# Nuio_Left_Keyboard_Rev_H_KeyboardNRF.net
KiCad netlist of a schematic drawn in Altium Designer
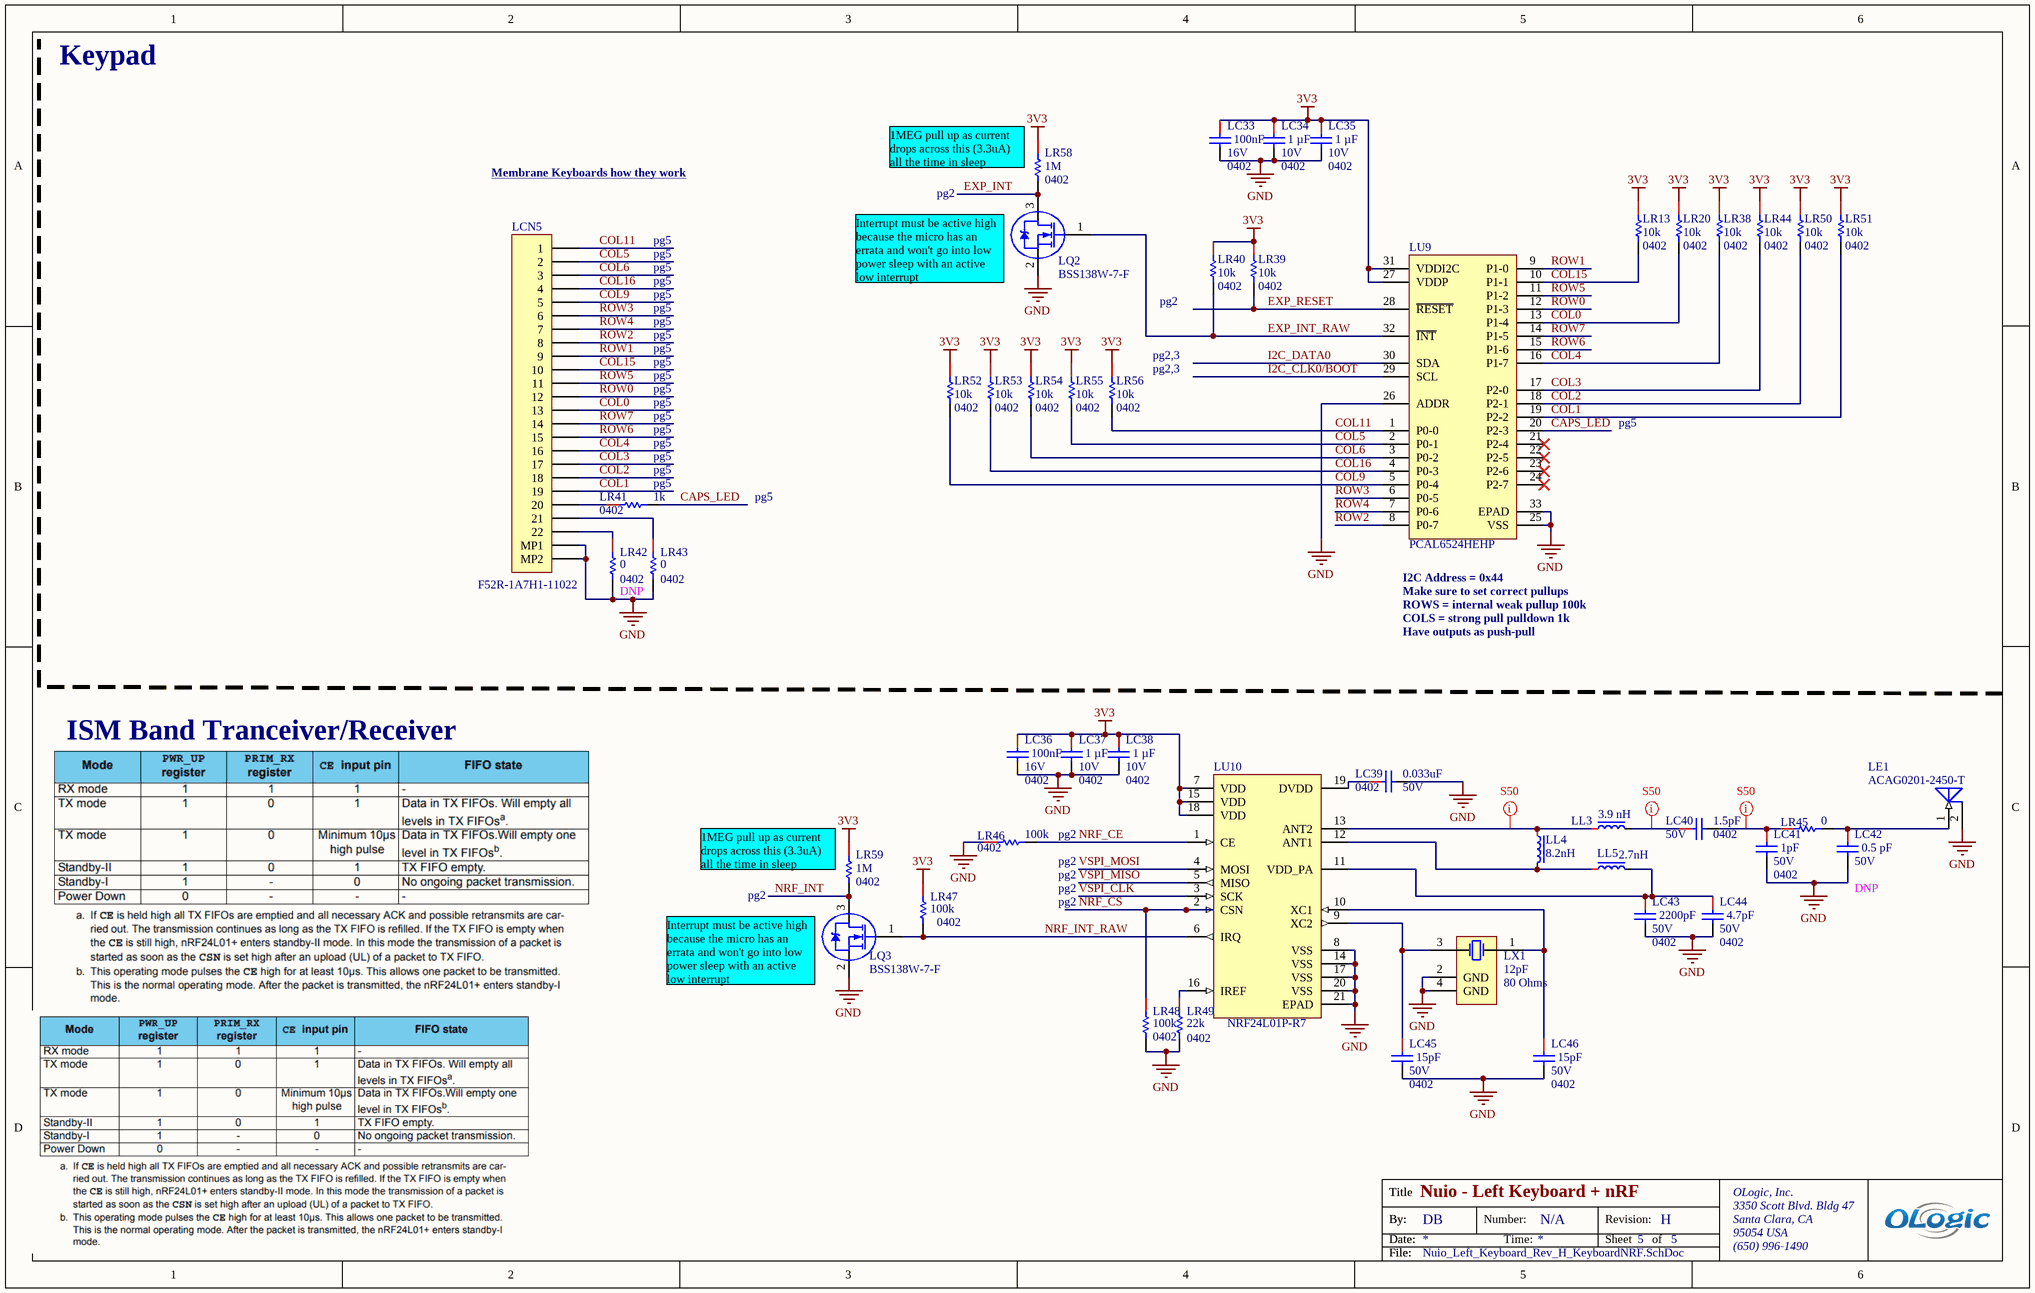
[diagram p0: Nuio_Left_Keyboard_Rev_H_KeyboardNRF.SchDoc]

(export (version "E")
  (design (tool "Eeschema 10.0.6"))
  (components
    (comp (ref "LC33")
      (value "CAP CER 0.1UF 16V X5R 0402")
      (footprint "CAPC0402(1005)_L")
      (description "±10% 16V Ceramic Capacitor X5R 0402 (1005 Metric)")
      (fields
        (field (name "PACKAGE (IMPERIAL)") "0402")
        (field (name "VOLTAGE (RATED)") "16V")
        (field (name "CAPACITANCE") "100nF")
        (field (name "MANUFACTURER") "Taiyo Yuden")
        (field (name "MANUFACTURER PART NUMBER") "EMK105BJ104KV-F")
      )
      (libsource (lib "OLogic Nexus Vault") (part "OL_Capacitor"))
    )
    (comp (ref "LC34")
      (value "CAP CER 1UF 10V X5R 0402")
      (footprint "CAPC0402(1005)_L")
      (description "±20% 10V Ceramic Capacitor X5R 0402 (1005 Metric)")
      (fields
        (field (name "PACKAGE (IMPERIAL)") "0402")
        (field (name "VOLTAGE (RATED)") "10V")
        (field (name "CAPACITANCE") "1 µF")
        (field (name "MANUFACTURER PART NUMBER") "CC0402MRX5R6BB105")
        (field (name "TOLERANCE") "±20%")
      )
      (libsource (lib "OLogic Nexus Vault") (part "OL_Capacitor"))
    )
    (comp (ref "LC35")
      (value "CAP CER 1UF 10V X5R 0402")
      (footprint "CAPC0402(1005)_L")
      (description "±20% 10V Ceramic Capacitor X5R 0402 (1005 Metric)")
      (fields
        (field (name "PACKAGE (IMPERIAL)") "0402")
        (field (name "VOLTAGE (RATED)") "10V")
        (field (name "CAPACITANCE") "1 µF")
        (field (name "MANUFACTURER PART NUMBER") "CC0402MRX5R6BB105")
        (field (name "TOLERANCE") "±20%")
      )
      (libsource (lib "OLogic Nexus Vault") (part "OL_Capacitor"))
    )
    (comp (ref "LC36")
      (value "CAP CER 0.1UF 16V X5R 0402")
      (footprint "CAPC0402(1005)_L")
      (description "±10% 16V Ceramic Capacitor X5R 0402 (1005 Metric)")
      (fields
        (field (name "PACKAGE (IMPERIAL)") "0402")
        (field (name "VOLTAGE (RATED)") "16V")
        (field (name "CAPACITANCE") "100nF")
        (field (name "MANUFACTURER") "Taiyo Yuden")
        (field (name "MANUFACTURER PART NUMBER") "EMK105BJ104KV-F")
      )
      (libsource (lib "OLogic Nexus Vault") (part "OL_Capacitor"))
    )
    (comp (ref "LC37")
      (value "CAP CER 1UF 10V X5R 0402")
      (footprint "CAPC0402(1005)_L")
      (description "±20% 10V Ceramic Capacitor X5R 0402 (1005 Metric)")
      (fields
        (field (name "PACKAGE (IMPERIAL)") "0402")
        (field (name "VOLTAGE (RATED)") "10V")
        (field (name "CAPACITANCE") "1 µF")
        (field (name "MANUFACTURER PART NUMBER") "CC0402MRX5R6BB105")
        (field (name "TOLERANCE") "±20%")
      )
      (libsource (lib "OLogic Nexus Vault") (part "OL_Capacitor"))
    )
    (comp (ref "LC38")
      (value "CAP CER 1UF 10V X5R 0402")
      (footprint "CAPC0402(1005)_L")
      (description "±20% 10V Ceramic Capacitor X5R 0402 (1005 Metric)")
      (fields
        (field (name "PACKAGE (IMPERIAL)") "0402")
        (field (name "VOLTAGE (RATED)") "10V")
        (field (name "CAPACITANCE") "1 µF")
        (field (name "MANUFACTURER PART NUMBER") "CC0402MRX5R6BB105")
        (field (name "TOLERANCE") "±20%")
      )
      (libsource (lib "OLogic Nexus Vault") (part "OL_Capacitor"))
    )
    (comp (ref "LC39")
      (value "0.033uF")
      (footprint "CAPC0402(1005)_L")
      (description "CAP CER 0.033UF 50V 10% X7R 0402")
      (fields
        (field (name "VOLTAGE (RATED)") "50V")
        (field (name "PACKAGE (IMPERIAL)") "0402")
        (field (name "TOLERANCE") "10%")
      )
      (libsource (lib "OLogic Nexus Vault") (part "=Capacitance"))
    )
    (comp (ref "LC40")
      (value "1.5pF")
      (footprint "CAPC0402(1005)_L")
      (description "CAP CER 1.5PF 50V NP0 0402")
      (fields
        (field (name "VOLTAGE (RATED)") "50V")
        (field (name "PACKAGE (IMPERIAL)") "0402")
        (field (name "TOLERANCE") "5%")
      )
      (libsource (lib "OLogic Nexus Vault") (part "=Capacitance"))
    )
    (comp (ref "LC41")
      (value "1pF")
      (footprint "CAPC0402(1005)_L")
      (description "CAP CER 1PF 50V NP0 0402")
      (fields
        (field (name "VOLTAGE (RATED)") "50V")
        (field (name "PACKAGE (IMPERIAL)") "0402")
        (field (name "TOLERANCE") "5%")
      )
      (libsource (lib "OLogic Nexus Vault") (part "=Capacitance"))
    )
    (comp (ref "LC42")
      (value "CAP CER 0.5PF 50V C0G/NP0 0402")
      (footprint "CAPC0402(1005)_L")
      (description "0.5 pF ±0.1pF 50V Ceramic Capacitor C0G, NP0 0402 (1005 Metric)")
      (fields
        (field (name "CAPACITANCE") "0.5 pF")
        (field (name "VOLTAGE - RATED") "50V")
        (field (name "TOLERANCE") "±0.1pF")
        (field (name "MANUFACTURER PART NUMBER") "QSCF500Q0R5B1GV001T")
      )
      (libsource (lib "OLogic Nexus Vault") (part "OL_Capacitor"))
    )
    (comp (ref "LC43")
      (value "2200pF")
      (footprint "CAPC0402(1005)_L")
      (description "CAP CER 2200PF 50V 10% X7R 0402")
      (fields
        (field (name "VOLTAGE (RATED)") "50V")
        (field (name "PACKAGE (IMPERIAL)") "0402")
        (field (name "TOLERANCE") "10%")
      )
      (libsource (lib "OLogic Nexus Vault") (part "=Capacitance"))
    )
    (comp (ref "LC44")
      (value "4.7pF")
      (footprint "CAPC0402(1005)_L")
      (description "CAP CER 4.7pF 50V 5% NP0 0402")
      (fields
        (field (name "VOLTAGE (RATED)") "50V")
        (field (name "PACKAGE (IMPERIAL)") "0402")
        (field (name "TOLERANCE") "5%")
      )
      (libsource (lib "OLogic Nexus Vault") (part "=Capacitance"))
    )
    (comp (ref "LC45")
      (value "15pF")
      (footprint "CAPC0402(1005)_L")
      (description "CAP CER 15PF 50V C0G/NP0 0402")
      (fields
        (field (name "VOLTAGE (RATED)") "50V")
        (field (name "PACKAGE (IMPERIAL)") "0402")
        (field (name "TOLERANCE") "5%")
      )
      (libsource (lib "OLogic Nexus Vault") (part "=Capacitance"))
    )
    (comp (ref "LC46")
      (value "15pF")
      (footprint "CAPC0402(1005)_L")
      (description "CAP CER 15PF 50V C0G/NP0 0402")
      (fields
        (field (name "VOLTAGE (RATED)") "50V")
        (field (name "PACKAGE (IMPERIAL)") "0402")
        (field (name "TOLERANCE") "5%")
      )
      (libsource (lib "OLogic Nexus Vault") (part "=Capacitance"))
    )
    (comp (ref "LCN5")
      (value "F52R-1A7H1-11022")
      (footprint "F52R-1A7H1-11022")
      (description "FLEX CONNECTOR, 1.00MM PITCH, HE")
      (fields (field (name "MANUFACTURER") "Amphenol ICC (FCI)"))
      (libsource (lib "OLogic Nexus Vault") (part "F52R-1A7H1-11022"))
    )
    (comp (ref "LE1")
      (value "ACAG0201-2450-T")
      (footprint "ACAG0201-2450-T")
      (description "RF ANT 2.4GHZ CHIP SOLDER SMD")
      (fields (field (name "MANUFACTURER") "Abracon LLC"))
      (libsource (lib "OLogic Nexus Vault") (part "RF ANT Trace - OLogic"))
    )
    (comp (ref "LL3")
      (value "FIXED IND 3.9NH 0402")
      (footprint "FP-LQG15HH_02-IPC_C")
      (description "Inductor RF Chip 0.0039uH 0.1nH 100MHz 8Q-Factor Air 0.75A 0.14Ohm DCR 0402 T/R")
      (fields
        (field (name "INDUCTANCE") "3.9 nH")
        (field (name "MANUFACTURER PART NUMBER") "Murata Electronics")
        (field (name "MANUFACTURER") "LQG15HS3N9B02D")
      )
      (libsource (lib "OLogic Nexus Vault") (part "OL_Inductor_sm"))
    )
    (comp (ref "LL4")
      (value "FIXED IND 8.2NH 550MA 240MOHM SM")
      (footprint "Inductor0402(1005)_L")
      (description "8.2 nH Unshielded Multilayer Inductor 550 mA 240mOhm Max 0402 (1005 Metric)")
      (fields
        (field (name "INDUCTANCE") "8.2nH")
        (field (name "MANUFACTURER PART NUMBER") "LQG15HS8N2J02D")
        (field (name "MANUFACTURER") "Murata Electronics")
      )
      (libsource (lib "OLogic Nexus Vault") (part "OL_Inductor_sm"))
    )
    (comp (ref "LL5")
      (value "FIXED IND 2.7NH 800MA 150MOHM SM")
      (footprint "Inductor0402(1005)_L")
      (description "2.7 nH Unshielded Multilayer Inductor 800 mA 150mOhm Max 0402 (1005 Metric)")
      (fields
        (field (name "INDUCTANCE") "2.7nH")
        (field (name "MANUFACTURER PART NUMBER") "LQG15HS2N7S02D")
        (field (name "MANUFACTURER") "Murata Electronics")
      )
      (libsource (lib "OLogic Nexus Vault") (part "OL_Inductor_sm"))
    )
    (comp (ref "LQ2")
      (value "BSS138W-7-F")
      (footprint "DIOD-SOT323-3_V")
      (description "DIODES INC. - BSS138W-7-F. - BSS FAMILY SOT323 T&R 3K ROHS COMPLIANT: YES")
      (fields (field (name "VOLTAGE") "50V") (field (name "POWER") "200mW"))
      (libsource (lib "Nuio_Left_Keyboard_Rev_H") (part "CMP-00300-01"))
    )
    (comp (ref "LQ3")
      (value "BSS138W-7-F")
      (footprint "DIOD-SOT323-3_V")
      (description "DIODES INC. - BSS138W-7-F. - BSS FAMILY SOT323 T&R 3K ROHS COMPLIANT: YES")
      (fields (field (name "VOLTAGE") "50V") (field (name "POWER") "200mW"))
      (libsource (lib "Nuio_Left_Keyboard_Rev_H") (part "CMP-00300-01"))
    )
    (comp (ref "LR13")
      (value "RES SMD 10K OHM 1% 1/16W 0402")
      (footprint "RESC0402_YAGEO")
      (fields
        (field (name "RESISTANCE") "10k")
        (field (name "PACKAGE (IMPERIAL)") "0402")
        (field (name "MANUFACTURER") "Yageo")
        (field (name "TOLERANCE") "1%")
        (field (name "MANUFACTURER PART NUMBER") "AT0402FRE0710KL")
      )
      (libsource (lib "OLogic Nexus Vault") (part "OL_Resistor"))
    )
    (comp (ref "LR20")
      (value "RES SMD 10K OHM 1% 1/16W 0402")
      (footprint "RESC0402_YAGEO")
      (fields
        (field (name "RESISTANCE") "10k")
        (field (name "PACKAGE (IMPERIAL)") "0402")
        (field (name "MANUFACTURER") "Yageo")
        (field (name "TOLERANCE") "1%")
        (field (name "MANUFACTURER PART NUMBER") "AT0402FRE0710KL")
      )
      (libsource (lib "OLogic Nexus Vault") (part "OL_Resistor"))
    )
    (comp (ref "LR38")
      (value "RES SMD 10K OHM 1% 1/16W 0402")
      (footprint "RESC0402_YAGEO")
      (fields
        (field (name "RESISTANCE") "10k")
        (field (name "PACKAGE (IMPERIAL)") "0402")
        (field (name "MANUFACTURER") "Yageo")
        (field (name "TOLERANCE") "1%")
        (field (name "MANUFACTURER PART NUMBER") "AT0402FRE0710KL")
      )
      (libsource (lib "OLogic Nexus Vault") (part "OL_Resistor"))
    )
    (comp (ref "LR39")
      (value "RES SMD 10K OHM 1% 1/16W 0402")
      (footprint "RESC0402_YAGEO")
      (fields
        (field (name "RESISTANCE") "10k")
        (field (name "PACKAGE (IMPERIAL)") "0402")
        (field (name "MANUFACTURER") "Yageo")
        (field (name "TOLERANCE") "1%")
        (field (name "MANUFACTURER PART NUMBER") "AT0402FRE0710KL")
      )
      (libsource (lib "OLogic Nexus Vault") (part "OL_Resistor"))
    )
    (comp (ref "LR40")
      (value "RES SMD 10K OHM 1% 1/16W 0402")
      (footprint "RESC0402_YAGEO")
      (fields
        (field (name "RESISTANCE") "10k")
        (field (name "PACKAGE (IMPERIAL)") "0402")
        (field (name "MANUFACTURER") "Yageo")
        (field (name "TOLERANCE") "1%")
        (field (name "MANUFACTURER PART NUMBER") "AT0402FRE0710KL")
      )
      (libsource (lib "OLogic Nexus Vault") (part "OL_Resistor"))
    )
    (comp (ref "LR41")
      (value "RES SMD 1K OHM 1% 1/16W 0402")
      (footprint "RESC0402(1005)_L")
      (fields
        (field (name "RESISTANCE") "1k")
        (field (name "PACKAGE (IMPERIAL)") "0402")
        (field (name "POWER") "63mW")
        (field (name "MANUFACTURER") "Yageo")
        (field (name "TOLERANCE") "1%")
      )
      (libsource (lib "OLogic Nexus Vault") (part "OL_Resistor"))
    )
    (comp (ref "LR42")
      (value "RES 0 OHM JUMPER 1/16W 0402")
      (footprint "RESC0402(1005)_L")
      (description "0 Ohms Jumper Chip Resistor 0402 (1005 Metric) Automotive AEC-Q200 Thick Film")
      (fields
        (field (name "PACKAGE (IMPERIAL)") "0402")
        (field (name "RESISTANCE") "0")
        (field (name "POWER") "63mW")
        (field (name "TOLERANCE") "0%")
      )
      (libsource (lib "OLogic Nexus Vault") (part "=Resistance"))
    )
    (comp (ref "LR43")
      (value "RES 0 OHM JUMPER 1/16W 0402")
      (footprint "RESC0402(1005)_L")
      (description "0 Ohms Jumper Chip Resistor 0402 (1005 Metric) Automotive AEC-Q200 Thick Film")
      (fields
        (field (name "PACKAGE (IMPERIAL)") "0402")
        (field (name "RESISTANCE") "0")
        (field (name "POWER") "63mW")
        (field (name "TOLERANCE") "0%")
      )
      (libsource (lib "OLogic Nexus Vault") (part "=Resistance"))
    )
    (comp (ref "LR44")
      (value "RES SMD 10K OHM 1% 1/16W 0402")
      (footprint "RESC0402_YAGEO")
      (fields
        (field (name "RESISTANCE") "10k")
        (field (name "PACKAGE (IMPERIAL)") "0402")
        (field (name "MANUFACTURER") "Yageo")
        (field (name "TOLERANCE") "1%")
        (field (name "MANUFACTURER PART NUMBER") "AT0402FRE0710KL")
      )
      (libsource (lib "OLogic Nexus Vault") (part "OL_Resistor"))
    )
    (comp (ref "LR45")
      (value "RES 0 OHM JUMPER 1/16W 0402")
      (footprint "RESC0402(1005)_L")
      (description "0 Ohms Jumper Chip Resistor 0402 (1005 Metric) Automotive AEC-Q200 Thick Film")
      (fields (field (name "RESISTANCE") "0") (field (name "POWER") "63mW") (field (name "TOLERANCE") "0%"))
      (libsource (lib "OLogic Nexus Vault") (part "=Resistance"))
    )
    (comp (ref "LR46")
      (value "100k")
      (footprint "RESC0402(1005)_L")
      (description "±1% 0.063W, 1/16W Chip Resistor 0402 (1005 Metric) Moisture Resistant Thick Film")
      (fields
        (field (name "CASE CODE (IMPERIAL)") "0402")
        (field (name "TOLERANCE") "1%")
        (field (name "MANUFACTURER") "YAGEO")
      )
      (libsource (lib "OLogic Nexus Vault") (part "=Resistance"))
    )
    (comp (ref "LR47")
      (value "100k")
      (footprint "RESC0402(1005)_L")
      (description "±1% 0.063W, 1/16W Chip Resistor 0402 (1005 Metric) Moisture Resistant Thick Film")
      (fields
        (field (name "CASE CODE (IMPERIAL)") "0402")
        (field (name "TOLERANCE") "1%")
        (field (name "MANUFACTURER") "YAGEO")
      )
      (libsource (lib "OLogic Nexus Vault") (part "=Resistance"))
    )
    (comp (ref "LR48")
      (value "100k")
      (footprint "RESC0402(1005)_L")
      (description "±1% 0.063W, 1/16W Chip Resistor 0402 (1005 Metric) Moisture Resistant Thick Film")
      (fields
        (field (name "CASE CODE (IMPERIAL)") "0402")
        (field (name "TOLERANCE") "1%")
        (field (name "MANUFACTURER") "YAGEO")
      )
      (libsource (lib "OLogic Nexus Vault") (part "=Resistance"))
    )
    (comp (ref "LR49")
      (value "22K")
      (footprint "RESC0402(1005)_L")
      (description "RES SMD 22K OHM 1% 1/16W 0402")
      (fields
        (field (name "PACKAGE (IMPERIAL)") "0402")
        (field (name "RESISTANCE") "22k")
        (field (name "POWER") "63mW")
        (field (name "TOLERANCE") "1%")
      )
      (libsource (lib "OLogic Nexus Vault") (part "=Resistance"))
    )
    (comp (ref "LR50")
      (value "RES SMD 10K OHM 1% 1/16W 0402")
      (footprint "RESC0402_YAGEO")
      (fields
        (field (name "RESISTANCE") "10k")
        (field (name "PACKAGE (IMPERIAL)") "0402")
        (field (name "MANUFACTURER") "Yageo")
        (field (name "TOLERANCE") "1%")
        (field (name "MANUFACTURER PART NUMBER") "AT0402FRE0710KL")
      )
      (libsource (lib "OLogic Nexus Vault") (part "OL_Resistor"))
    )
    (comp (ref "LR51")
      (value "RES SMD 10K OHM 1% 1/16W 0402")
      (footprint "RESC0402_YAGEO")
      (fields
        (field (name "RESISTANCE") "10k")
        (field (name "PACKAGE (IMPERIAL)") "0402")
        (field (name "MANUFACTURER") "Yageo")
        (field (name "TOLERANCE") "1%")
        (field (name "MANUFACTURER PART NUMBER") "AT0402FRE0710KL")
      )
      (libsource (lib "OLogic Nexus Vault") (part "OL_Resistor"))
    )
    (comp (ref "LR52")
      (value "RES SMD 10K OHM 1% 1/16W 0402")
      (footprint "RESC0402_YAGEO")
      (fields
        (field (name "RESISTANCE") "10k")
        (field (name "PACKAGE (IMPERIAL)") "0402")
        (field (name "MANUFACTURER") "Yageo")
        (field (name "TOLERANCE") "1%")
        (field (name "MANUFACTURER PART NUMBER") "AT0402FRE0710KL")
      )
      (libsource (lib "OLogic Nexus Vault") (part "OL_Resistor"))
    )
    (comp (ref "LR53")
      (value "RES SMD 10K OHM 1% 1/16W 0402")
      (footprint "RESC0402_YAGEO")
      (fields
        (field (name "RESISTANCE") "10k")
        (field (name "PACKAGE (IMPERIAL)") "0402")
        (field (name "MANUFACTURER") "Yageo")
        (field (name "TOLERANCE") "1%")
        (field (name "MANUFACTURER PART NUMBER") "AT0402FRE0710KL")
      )
      (libsource (lib "OLogic Nexus Vault") (part "OL_Resistor"))
    )
    (comp (ref "LR54")
      (value "RES SMD 10K OHM 1% 1/16W 0402")
      (footprint "RESC0402_YAGEO")
      (fields
        (field (name "RESISTANCE") "10k")
        (field (name "PACKAGE (IMPERIAL)") "0402")
        (field (name "MANUFACTURER") "Yageo")
        (field (name "TOLERANCE") "1%")
        (field (name "MANUFACTURER PART NUMBER") "AT0402FRE0710KL")
      )
      (libsource (lib "OLogic Nexus Vault") (part "OL_Resistor"))
    )
    (comp (ref "LR55")
      (value "RES SMD 10K OHM 1% 1/16W 0402")
      (footprint "RESC0402_YAGEO")
      (fields
        (field (name "RESISTANCE") "10k")
        (field (name "PACKAGE (IMPERIAL)") "0402")
        (field (name "MANUFACTURER") "Yageo")
        (field (name "TOLERANCE") "1%")
        (field (name "MANUFACTURER PART NUMBER") "AT0402FRE0710KL")
      )
      (libsource (lib "OLogic Nexus Vault") (part "OL_Resistor"))
    )
    (comp (ref "LR56")
      (value "RES SMD 10K OHM 1% 1/16W 0402")
      (footprint "RESC0402_YAGEO")
      (fields
        (field (name "RESISTANCE") "10k")
        (field (name "PACKAGE (IMPERIAL)") "0402")
        (field (name "MANUFACTURER") "Yageo")
        (field (name "TOLERANCE") "1%")
        (field (name "MANUFACTURER PART NUMBER") "AT0402FRE0710KL")
      )
      (libsource (lib "OLogic Nexus Vault") (part "OL_Resistor"))
    )
    (comp (ref "LR58")
      (value "RES 1M OHM 1% 1/16W 0402")
      (footprint "RESC0402(1005)_L")
      (description "1 MOhms ±1% 0.063W, 1/16W Chip Resistor 0402 (1005 Metric) Moisture Resistant Thick Film")
      (fields
        (field (name "RESISTANCE") "1M")
        (field (name "CASE/PACKAGE") "0402")
        (field (name "MANUFACTURER") "YAGEO")
        (field (name "MANUFACTURER PART NUMBER") "RC0402FR-071ML")
      )
      (libsource (lib "OLogic Nexus Vault") (part "OL_Resistor"))
    )
    (comp (ref "LR59")
      (value "RES 1M OHM 1% 1/16W 0402")
      (footprint "RESC0402(1005)_L")
      (description "1 MOhms ±1% 0.063W, 1/16W Chip Resistor 0402 (1005 Metric) Moisture Resistant Thick Film")
      (fields
        (field (name "RESISTANCE") "1M")
        (field (name "CASE/PACKAGE") "0402")
        (field (name "MANUFACTURER") "YAGEO")
        (field (name "MANUFACTURER PART NUMBER") "RC0402FR-071ML")
      )
      (libsource (lib "OLogic Nexus Vault") (part "OL_Resistor"))
    )
    (comp (ref "LU9")
      (value "PCAL6524HEHP")
      (footprint "QFN50P500X500X60_HS-33N")
      (description "Ultra low-voltage translating 24-bit Fm+ I²C-bus/SMBus I/O expander")
      (libsource (lib "OLogic Nexus Vault") (part "PCAL6524HEHP"))
    )
    (comp (ref "LU10")
      (value "NRF24L01P-R7")
      (footprint "QFN50P400X400X95_HS-21N")
      (description "IC RF TXRX ISM>1GHZ 20VFQFN")
      (fields (field (name "MANUFACTURER") "Nordic Semiconductor ASA"))
      (libsource (lib "OLogic Nexus Vault") (part "NRF24L01P-R7"))
    )
    (comp (ref "LX1")
      (value "ECS-160-12-33-AGN-TR3")
      (footprint "ECS-160-12-33-AGN-TR3")
      (description "CRYSTAL 16.0000MHZ 12PF SMD")
      (fields
        (field (name "LOAD CAPACITANCE") "12pF")
        (field (name "ESR") "80 Ohms")
        (field (name "MANUFACTURER") "ECS Inc.")
      )
      (libsource (lib "OLogic Nexus Vault") (part "OL_Crystal"))
    )
  )
  (nets
    (net (code "1") (name "/CAPS_LED") (class "Default")
      (node (ref "LR41") (pin "2") (pinfunction "2_2") (pintype "passive"))
      (node (ref "LU9") (pin "20") (pinfunction "P2-3_20") (pintype "passive"))
    )
    (net (code "2") (name "/COL0") (class "Default")
      (node (ref "LCN5") (pin "13") (pinfunction "13_13") (pintype "passive"))
      (node (ref "LR20") (pin "2") (pinfunction "2_2") (pintype "passive"))
      (node (ref "LU9") (pin "13") (pinfunction "P1-4_13") (pintype "passive"))
    )
    (net (code "3") (name "/COL1") (class "Default")
      (node (ref "LCN5") (pin "19") (pinfunction "19_19") (pintype "passive"))
      (node (ref "LR51") (pin "2") (pinfunction "2_2") (pintype "passive"))
      (node (ref "LU9") (pin "19") (pinfunction "P2-2_19") (pintype "passive"))
    )
    (net (code "4") (name "/COL2") (class "Default")
      (node (ref "LCN5") (pin "18") (pinfunction "18_18") (pintype "passive"))
      (node (ref "LR50") (pin "2") (pinfunction "2_2") (pintype "passive"))
      (node (ref "LU9") (pin "18") (pinfunction "P2-1_18") (pintype "passive"))
    )
    (net (code "5") (name "/COL3") (class "Default")
      (node (ref "LCN5") (pin "17") (pinfunction "17_17") (pintype "passive"))
      (node (ref "LR44") (pin "2") (pinfunction "2_2") (pintype "passive"))
      (node (ref "LU9") (pin "17") (pinfunction "P2-0_17") (pintype "passive"))
    )
    (net (code "6") (name "/COL4") (class "Default")
      (node (ref "LCN5") (pin "16") (pinfunction "16_16") (pintype "passive"))
      (node (ref "LR38") (pin "2") (pinfunction "2_2") (pintype "passive"))
      (node (ref "LU9") (pin "16") (pinfunction "P1-7_16") (pintype "passive"))
    )
    (net (code "7") (name "/COL5") (class "Default")
      (node (ref "LCN5") (pin "2") (pinfunction "2_2") (pintype "passive"))
      (node (ref "LR55") (pin "2") (pinfunction "2_2") (pintype "passive"))
      (node (ref "LU9") (pin "2") (pinfunction "P0-1_2") (pintype "passive"))
    )
    (net (code "8") (name "/COL6") (class "Default")
      (node (ref "LCN5") (pin "3") (pinfunction "3_3") (pintype "passive"))
      (node (ref "LR54") (pin "2") (pinfunction "2_2") (pintype "passive"))
      (node (ref "LU9") (pin "3") (pinfunction "P0-2_3") (pintype "passive"))
    )
    (net (code "9") (name "/COL9") (class "Default")
      (node (ref "LCN5") (pin "5") (pinfunction "5_5") (pintype "passive"))
      (node (ref "LR52") (pin "2") (pinfunction "2_2") (pintype "passive"))
      (node (ref "LU9") (pin "5") (pinfunction "P0-4_5") (pintype "passive"))
    )
    (net (code "10") (name "/COL11") (class "Default")
      (node (ref "LCN5") (pin "1") (pinfunction "1_1") (pintype "passive"))
      (node (ref "LR56") (pin "2") (pinfunction "2_2") (pintype "passive"))
      (node (ref "LU9") (pin "1") (pinfunction "P0-0_1") (pintype "passive"))
    )
    (net (code "11") (name "/COL15") (class "Default")
      (node (ref "LCN5") (pin "10") (pinfunction "10_10") (pintype "passive"))
      (node (ref "LR13") (pin "2") (pinfunction "2_2") (pintype "passive"))
      (node (ref "LU9") (pin "10") (pinfunction "P1-1_10") (pintype "passive"))
    )
    (net (code "12") (name "/COL16") (class "Default")
      (node (ref "LCN5") (pin "4") (pinfunction "4_4") (pintype "passive"))
      (node (ref "LR53") (pin "2") (pinfunction "2_2") (pintype "passive"))
      (node (ref "LU9") (pin "4") (pinfunction "P0-3_4") (pintype "passive"))
    )
    (net (code "13") (name "/EXP_INT") (class "Default")
      (node (ref "LQ2") (pin "3") (pinfunction "D_3") (pintype "passive"))
      (node (ref "LR58") (pin "2") (pinfunction "2_2") (pintype "passive"))
    )
    (net (code "14") (name "/EXP_INT_RAW") (class "Default")
      (node (ref "LQ2") (pin "1") (pinfunction "G_1") (pintype "passive"))
      (node (ref "LR40") (pin "2") (pinfunction "2_2") (pintype "passive"))
      (node (ref "LU9") (pin "32") (pinfunction "~{INT}_32") (pintype "passive"))
    )
    (net (code "15") (name "/EXP_RESET") (class "Default")
      (node (ref "LR39") (pin "2") (pinfunction "2_2") (pintype "passive"))
      (node (ref "LU9") (pin "28") (pinfunction "~{RESET}_28") (pintype "passive"))
    )
    (net (code "16") (name "/I2C_CLK0{slash}BOOT") (class "Default")
      (node (ref "LU9") (pin "29") (pinfunction "SCL_29") (pintype "passive"))
    )
    (net (code "17") (name "/I2C_DATA0") (class "Default")
      (node (ref "LU9") (pin "30") (pinfunction "SDA_30") (pintype "passive"))
    )
    (net (code "18") (name "/NRF_CE") (class "Default")
      (node (ref "LR46") (pin "2") (pinfunction "2_2") (pintype "passive"))
      (node (ref "LU10") (pin "1") (pinfunction "CE_1") (pintype "input"))
    )
    (net (code "19") (name "/NRF_CS") (class "Default")
      (node (ref "LR48") (pin "1") (pinfunction "1_1") (pintype "passive"))
      (node (ref "LU10") (pin "2") (pinfunction "CSN_2") (pintype "input"))
    )
    (net (code "20") (name "/NRF_INT") (class "Default")
      (node (ref "LQ3") (pin "3") (pinfunction "D_3") (pintype "passive"))
      (node (ref "LR59") (pin "2") (pinfunction "2_2") (pintype "passive"))
    )
    (net (code "21") (name "/NRF_INT_RAW") (class "Default")
      (node (ref "LQ3") (pin "1") (pinfunction "G_1") (pintype "passive"))
      (node (ref "LR47") (pin "2") (pinfunction "2_2") (pintype "passive"))
      (node (ref "LU10") (pin "6") (pinfunction "IRQ_6") (pintype "output"))
    )
    (net (code "22") (name "/ROW0") (class "Default")
      (node (ref "LCN5") (pin "12") (pinfunction "12_12") (pintype "passive"))
      (node (ref "LU9") (pin "12") (pinfunction "P1-3_12") (pintype "passive"))
    )
    (net (code "23") (name "/ROW1") (class "Default")
      (node (ref "LCN5") (pin "9") (pinfunction "9_9") (pintype "passive"))
      (node (ref "LU9") (pin "9") (pinfunction "P1-0_9") (pintype "passive"))
    )
    (net (code "24") (name "/ROW2") (class "Default")
      (node (ref "LCN5") (pin "8") (pinfunction "8_8") (pintype "passive"))
      (node (ref "LU9") (pin "8") (pinfunction "P0-7_8") (pintype "passive"))
    )
    (net (code "25") (name "/ROW3") (class "Default")
      (node (ref "LCN5") (pin "6") (pinfunction "6_6") (pintype "passive"))
      (node (ref "LU9") (pin "6") (pinfunction "P0-5_6") (pintype "passive"))
    )
    (net (code "26") (name "/ROW4") (class "Default")
      (node (ref "LCN5") (pin "7") (pinfunction "7_7") (pintype "passive"))
      (node (ref "LU9") (pin "7") (pinfunction "P0-6_7") (pintype "passive"))
    )
    (net (code "27") (name "/ROW5") (class "Default")
      (node (ref "LCN5") (pin "11") (pinfunction "11_11") (pintype "passive"))
      (node (ref "LU9") (pin "11") (pinfunction "P1-2_11") (pintype "passive"))
    )
    (net (code "28") (name "/ROW6") (class "Default")
      (node (ref "LCN5") (pin "15") (pinfunction "15_15") (pintype "passive"))
      (node (ref "LU9") (pin "15") (pinfunction "P1-6_15") (pintype "passive"))
    )
    (net (code "29") (name "/ROW7") (class "Default")
      (node (ref "LCN5") (pin "14") (pinfunction "14_14") (pintype "passive"))
      (node (ref "LU9") (pin "14") (pinfunction "P1-5_14") (pintype "passive"))
    )
    (net (code "30") (name "/VSPI_CLK") (class "Default")
      (node (ref "LU10") (pin "3") (pinfunction "SCK_3") (pintype "input"))
    )
    (net (code "31") (name "/VSPI_MISO") (class "Default")
      (node (ref "LU10") (pin "5") (pinfunction "MISO_5") (pintype "output"))
    )
    (net (code "32") (name "/VSPI_MOSI") (class "Default")
      (node (ref "LU10") (pin "4") (pinfunction "MOSI_4") (pintype "input"))
    )
    (net (code "33") (name "3V3") (class "Default")
      (node (ref "LC33") (pin "1") (pinfunction "1_1") (pintype "passive"))
      (node (ref "LC34") (pin "1") (pinfunction "1_1") (pintype "passive"))
      (node (ref "LC35") (pin "1") (pinfunction "1_1") (pintype "passive"))
      (node (ref "LC36") (pin "1") (pinfunction "1_1") (pintype "passive"))
      (node (ref "LC37") (pin "1") (pinfunction "1_1") (pintype "passive"))
      (node (ref "LC38") (pin "1") (pinfunction "1_1") (pintype "passive"))
      (node (ref "LR13") (pin "1") (pinfunction "1_1") (pintype "passive"))
      (node (ref "LR20") (pin "1") (pinfunction "1_1") (pintype "passive"))
      (node (ref "LR38") (pin "1") (pinfunction "1_1") (pintype "passive"))
      (node (ref "LR39") (pin "1") (pinfunction "1_1") (pintype "passive"))
      (node (ref "LR40") (pin "1") (pinfunction "1_1") (pintype "passive"))
      (node (ref "LR44") (pin "1") (pinfunction "1_1") (pintype "passive"))
      (node (ref "LR47") (pin "1") (pinfunction "1_1") (pintype "passive"))
      (node (ref "LR50") (pin "1") (pinfunction "1_1") (pintype "passive"))
      (node (ref "LR51") (pin "1") (pinfunction "1_1") (pintype "passive"))
      (node (ref "LR52") (pin "1") (pinfunction "1_1") (pintype "passive"))
      (node (ref "LR53") (pin "1") (pinfunction "1_1") (pintype "passive"))
      (node (ref "LR54") (pin "1") (pinfunction "1_1") (pintype "passive"))
      (node (ref "LR55") (pin "1") (pinfunction "1_1") (pintype "passive"))
      (node (ref "LR56") (pin "1") (pinfunction "1_1") (pintype "passive"))
      (node (ref "LR58") (pin "1") (pinfunction "1_1") (pintype "passive"))
      (node (ref "LR59") (pin "1") (pinfunction "1_1") (pintype "passive"))
      (node (ref "LU10") (pin "15") (pinfunction "VDD_15") (pintype "power_in"))
      (node (ref "LU10") (pin "18") (pinfunction "VDD_18") (pintype "power_in"))
      (node (ref "LU10") (pin "7") (pinfunction "VDD_7") (pintype "power_in"))
      (node (ref "LU9") (pin "27") (pinfunction "VDDP_27") (pintype "passive"))
      (node (ref "LU9") (pin "31") (pinfunction "VDDI2C_31") (pintype "passive"))
    )
    (net (code "34") (name "GND") (class "Default")
      (node (ref "LC33") (pin "2") (pinfunction "2_2") (pintype "passive"))
      (node (ref "LC34") (pin "2") (pinfunction "2_2") (pintype "passive"))
      (node (ref "LC35") (pin "2") (pinfunction "2_2") (pintype "passive"))
      (node (ref "LC36") (pin "2") (pinfunction "2_2") (pintype "passive"))
      (node (ref "LC37") (pin "2") (pinfunction "2_2") (pintype "passive"))
      (node (ref "LC38") (pin "2") (pinfunction "2_2") (pintype "passive"))
      (node (ref "LC39") (pin "2") (pinfunction "2_2") (pintype "passive"))
      (node (ref "LC41") (pin "2") (pinfunction "2_2") (pintype "passive"))
      (node (ref "LC42") (pin "2") (pinfunction "2_2") (pintype "passive"))
      (node (ref "LC43") (pin "2") (pinfunction "2_2") (pintype "passive"))
      (node (ref "LC44") (pin "2") (pinfunction "2_2") (pintype "passive"))
      (node (ref "LC45") (pin "2") (pinfunction "2_2") (pintype "passive"))
      (node (ref "LC46") (pin "2") (pinfunction "2_2") (pintype "passive"))
      (node (ref "LCN5") (pin "MP1") (pinfunction "MP1_MP1") (pintype "passive"))
      (node (ref "LCN5") (pin "MP2") (pinfunction "MP2_MP2") (pintype "passive"))
      (node (ref "LE1") (pin "2") (pinfunction "GND_2") (pintype "power_in"))
      (node (ref "LQ2") (pin "2") (pinfunction "S_2") (pintype "passive"))
      (node (ref "LQ3") (pin "2") (pinfunction "S_2") (pintype "passive"))
      (node (ref "LR42") (pin "2") (pinfunction "2_2") (pintype "passive"))
      (node (ref "LR43") (pin "2") (pinfunction "2_2") (pintype "passive"))
      (node (ref "LR46") (pin "1") (pinfunction "1_1") (pintype "passive"))
      (node (ref "LR48") (pin "2") (pinfunction "2_2") (pintype "passive"))
      (node (ref "LR49") (pin "2") (pinfunction "2_2") (pintype "passive"))
      (node (ref "LU10") (pin "14") (pinfunction "VSS_14") (pintype "power_in"))
      (node (ref "LU10") (pin "17") (pinfunction "VSS_17") (pintype "power_in"))
      (node (ref "LU10") (pin "20") (pinfunction "VSS_20") (pintype "power_in"))
      (node (ref "LU10") (pin "21") (pinfunction "EPAD_21") (pintype "power_in"))
      (node (ref "LU10") (pin "8") (pinfunction "VSS_8") (pintype "power_in"))
      (node (ref "LU9") (pin "25") (pinfunction "VSS_25") (pintype "passive"))
      (node (ref "LU9") (pin "26") (pinfunction "ADDR_26") (pintype "passive"))
      (node (ref "LU9") (pin "33") (pinfunction "EPAD_33") (pintype "passive"))
      (node (ref "LX1") (pin "2") (pinfunction "GND_2") (pintype "passive"))
      (node (ref "LX1") (pin "4") (pinfunction "GND_4") (pintype "passive"))
    )
    (net (code "35") (name "Net-(LC40-Pad1)") (class "Default")
      (node (ref "LC40") (pin "1") (pinfunction "1_1") (pintype "passive"))
      (node (ref "LL3") (pin "2") (pinfunction "2_2") (pintype "passive"))
    )
    (net (code "36") (name "Net-(LC40-Pad2)") (class "Default")
      (node (ref "LC40") (pin "2") (pinfunction "2_2") (pintype "passive"))
      (node (ref "LC41") (pin "1") (pinfunction "1_1") (pintype "passive"))
      (node (ref "LR45") (pin "1") (pinfunction "1_1") (pintype "passive"))
    )
    (net (code "37") (name "Net-(LCN5-Pad20)") (class "Default")
      (node (ref "LCN5") (pin "20") (pinfunction "20_20") (pintype "passive"))
      (node (ref "LR41") (pin "1") (pinfunction "1_1") (pintype "passive"))
    )
    (net (code "38") (name "Net-(LCN5-Pad21)") (class "Default")
      (node (ref "LCN5") (pin "21") (pinfunction "21_21") (pintype "passive"))
      (node (ref "LR43") (pin "1") (pinfunction "1_1") (pintype "passive"))
    )
    (net (code "39") (name "Net-(LCN5-Pad22)") (class "Default")
      (node (ref "LCN5") (pin "22") (pinfunction "22_22") (pintype "passive"))
      (node (ref "LR42") (pin "1") (pinfunction "1_1") (pintype "passive"))
    )
    (net (code "40") (name "Net-(LE1-INPUT)") (class "Default")
      (node (ref "LC42") (pin "1") (pinfunction "1_1") (pintype "passive"))
      (node (ref "LE1") (pin "1") (pinfunction "INPUT_1") (pintype "input"))
      (node (ref "LR45") (pin "2") (pinfunction "2_2") (pintype "passive"))
    )
    (net (code "41") (name "Net-(LU10-ANT1)") (class "Default")
      (node (ref "LL4") (pin "2") (pinfunction "2_2") (pintype "passive"))
      (node (ref "LL5") (pin "1") (pinfunction "1_1") (pintype "passive"))
      (node (ref "LU10") (pin "12") (pinfunction "ANT1_12") (pintype "passive"))
    )
    (net (code "42") (name "Net-(LU10-ANT2)") (class "Default")
      (node (ref "LL3") (pin "1") (pinfunction "1_1") (pintype "passive"))
      (node (ref "LL4") (pin "1") (pinfunction "1_1") (pintype "passive"))
      (node (ref "LU10") (pin "13") (pinfunction "ANT2_13") (pintype "passive"))
    )
    (net (code "43") (name "Net-(LU10-DVDD)") (class "Default")
      (node (ref "LC39") (pin "1") (pinfunction "1_1") (pintype "passive"))
      (node (ref "LU10") (pin "19") (pinfunction "DVDD_19") (pintype "power_in"))
    )
    (net (code "44") (name "Net-(LU10-IREF)") (class "Default")
      (node (ref "LR49") (pin "1") (pinfunction "1_1") (pintype "passive"))
      (node (ref "LU10") (pin "16") (pinfunction "IREF_16") (pintype "input"))
    )
    (net (code "45") (name "Net-(LU10-VDD_PA)") (class "Default")
      (node (ref "LC43") (pin "1") (pinfunction "1_1") (pintype "passive"))
      (node (ref "LC44") (pin "1") (pinfunction "1_1") (pintype "passive"))
      (node (ref "LL5") (pin "2") (pinfunction "2_2") (pintype "passive"))
      (node (ref "LU10") (pin "11") (pinfunction "VDD_PA_11") (pintype "power_in"))
    )
    (net (code "46") (name "Net-(LU10-XC1)") (class "Default")
      (node (ref "LC46") (pin "1") (pinfunction "1_1") (pintype "passive"))
      (node (ref "LU10") (pin "10") (pinfunction "XC1_10") (pintype "input"))
      (node (ref "LX1") (pin "1") (pinfunction "OSC1_1") (pintype "passive"))
    )
    (net (code "47") (name "Net-(LU10-XC2)") (class "Default")
      (node (ref "LC45") (pin "1") (pinfunction "1_1") (pintype "passive"))
      (node (ref "LU10") (pin "9") (pinfunction "XC2_9") (pintype "output"))
      (node (ref "LX1") (pin "3") (pinfunction "OSC2_3") (pintype "passive"))
    )
    (net (code "48") (name "unconnected-(LU9-P2-4-Pad21)") (class "Default")
      (node (ref "LU9") (pin "21") (pinfunction "P2-4_21") (pintype "passive+no_connect"))
    )
    (net (code "49") (name "unconnected-(LU9-P2-5-Pad22)") (class "Default")
      (node (ref "LU9") (pin "22") (pinfunction "P2-5_22") (pintype "passive+no_connect"))
    )
    (net (code "50") (name "unconnected-(LU9-P2-6-Pad23)") (class "Default")
      (node (ref "LU9") (pin "23") (pinfunction "P2-6_23") (pintype "passive+no_connect"))
    )
    (net (code "51") (name "unconnected-(LU9-P2-7-Pad24)") (class "Default")
      (node (ref "LU9") (pin "24") (pinfunction "P2-7_24") (pintype "passive+no_connect"))
    )
  )
)
